# Power.net
KiCad netlist of a schematic drawn in Altium Designer
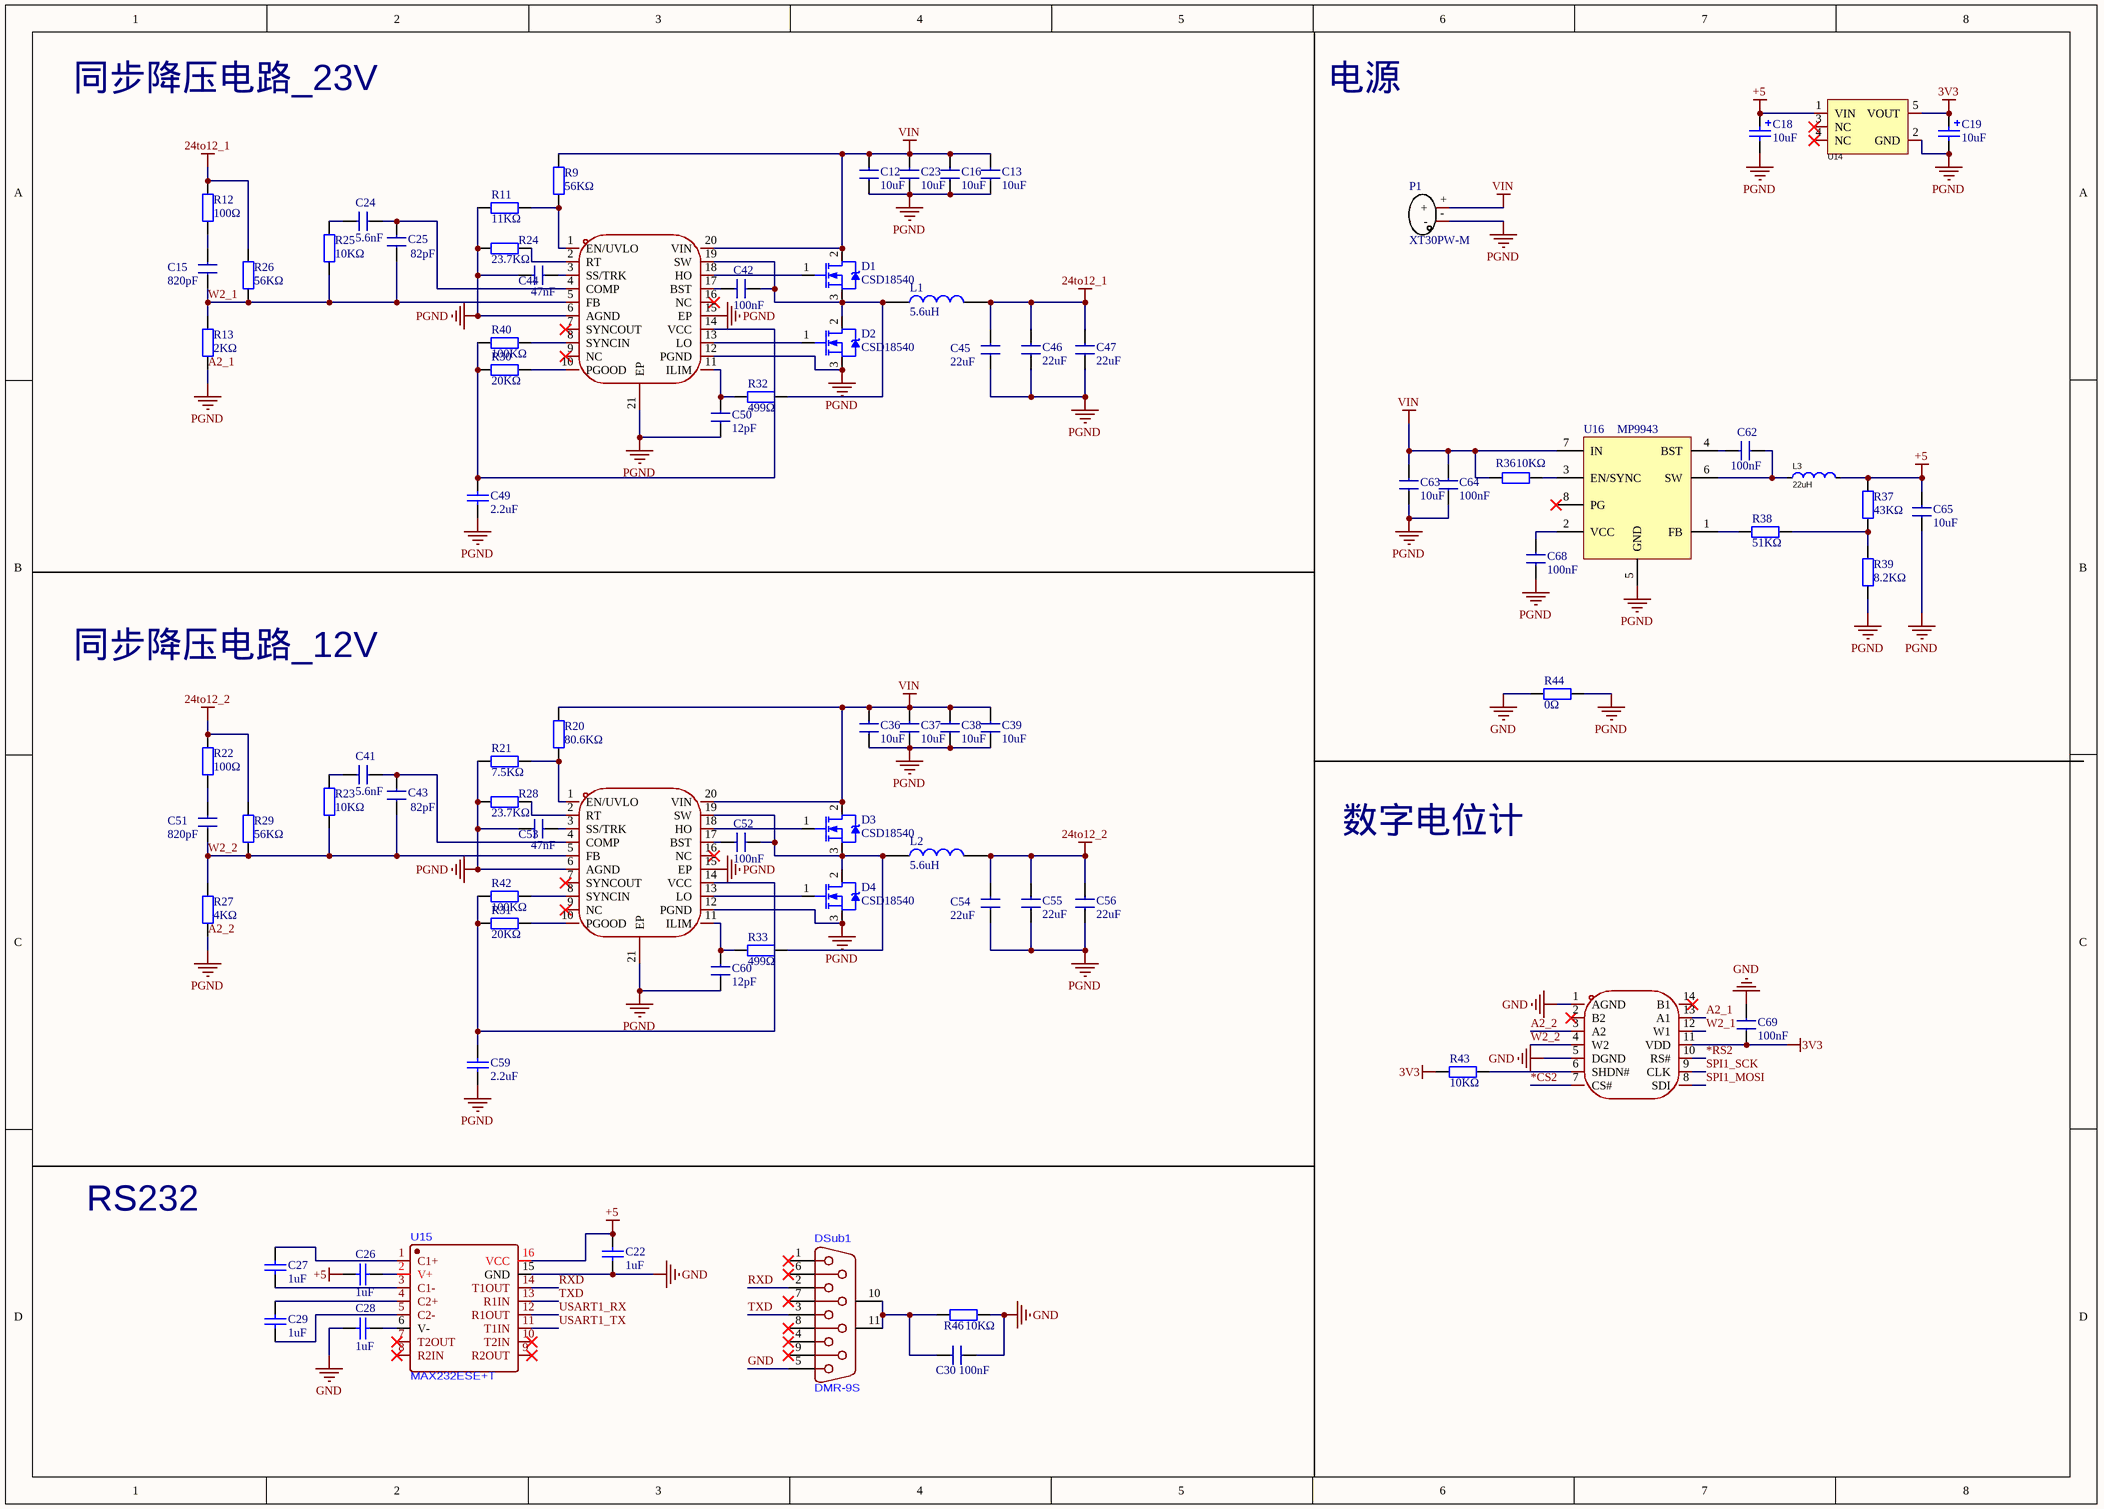
[diagram p0: Power.SchDoc]

(export (version "E")
  (design (tool "Eeschema 10.0.6"))
  (components
    (comp (ref "C12")
      (value "10uF")
      (footprint "1210")
      (description "1210贴片电容")
      (libsource (lib "Integrated_Library1") (part "1210贴片电容"))
    )
    (comp (ref "C13")
      (value "10uF")
      (footprint "1210")
      (description "1210贴片电容")
      (libsource (lib "En") (part "1210贴片电容"))
    )
    (comp (ref "C15")
      (value "820pF")
      (footprint "c0402")
      (description "贴片电容0402")
      (libsource (lib "Integrated_Library1") (part "0402贴片电容"))
    )
    (comp (ref "C16")
      (value "10uF")
      (footprint "1210")
      (description "1210贴片电容")
      (libsource (lib "En") (part "1210贴片电容"))
    )
    (comp (ref "C18")
      (value "10uF")
      (footprint "3216")
      (description "3216钽电容")
      (libsource (lib "Integrated_Library1") (part "3216钽电容"))
    )
    (comp (ref "C19")
      (value "10uF")
      (footprint "3216")
      (description "3216钽电容")
      (libsource (lib "Integrated_Library1") (part "3216钽电容"))
    )
    (comp (ref "C22")
      (value "1uF")
      (footprint "C 0603_M")
      (description "0603贴片电容")
      (libsource (lib "En") (part "0603贴片电容"))
    )
    (comp (ref "C23")
      (value "10uF")
      (footprint "1210")
      (description "1210贴片电容")
      (libsource (lib "En") (part "1210贴片电容"))
    )
    (comp (ref "C24")
      (value "5.6nF")
      (footprint "c0402")
      (description "贴片电容0402")
      (libsource (lib "Integrated_Library1") (part "0402贴片电容"))
    )
    (comp (ref "C25")
      (value "82pF")
      (footprint "c0402")
      (description "贴片电容0402")
      (libsource (lib "Integrated_Library1") (part "0402贴片电容"))
    )
    (comp (ref "C26")
      (value "1uF")
      (footprint "C 0603_M")
      (description "0603贴片电容")
      (libsource (lib "En") (part "0603贴片电容"))
    )
    (comp (ref "C27")
      (value "1uF")
      (footprint "C 0603_M")
      (description "0603贴片电容")
      (libsource (lib "En") (part "0603贴片电容"))
    )
    (comp (ref "C28")
      (value "1uF")
      (footprint "C 0603_M")
      (description "0603贴片电容")
      (libsource (lib "En") (part "0603贴片电容"))
    )
    (comp (ref "C29")
      (value "1uF")
      (footprint "C 0603_M")
      (description "0603贴片电容")
      (libsource (lib "En") (part "0603贴片电容"))
    )
    (comp (ref "C30")
      (value "100nF")
      (footprint "c0402")
      (description "贴片电容0402")
      (libsource (lib "Integrated_Library1") (part "0402贴片电容"))
    )
    (comp (ref "C36")
      (value "10uF")
      (footprint "1210")
      (description "1210贴片电容")
      (libsource (lib "Integrated_Library1") (part "1210贴片电容"))
    )
    (comp (ref "C37")
      (value "10uF")
      (footprint "1210")
      (description "1210贴片电容")
      (libsource (lib "En") (part "1210贴片电容"))
    )
    (comp (ref "C38")
      (value "10uF")
      (footprint "1210")
      (description "1210贴片电容")
      (libsource (lib "En") (part "1210贴片电容"))
    )
    (comp (ref "C39")
      (value "10uF")
      (footprint "1210")
      (description "1210贴片电容")
      (libsource (lib "En") (part "1210贴片电容"))
    )
    (comp (ref "C41")
      (value "5.6nF")
      (footprint "c0402")
      (description "贴片电容0402")
      (libsource (lib "Integrated_Library1") (part "0402贴片电容"))
    )
    (comp (ref "C42")
      (value "100nF")
      (footprint "C 0603_M")
      (description "贴片电容0402")
      (libsource (lib "Integrated_Library1") (part "0402贴片电容"))
    )
    (comp (ref "C43")
      (value "82pF")
      (footprint "c0402")
      (description "贴片电容0402")
      (libsource (lib "Integrated_Library1") (part "0402贴片电容"))
    )
    (comp (ref "C44")
      (value "47nF")
      (footprint "c0402")
      (description "贴片电容0402")
      (libsource (lib "Integrated_Library1") (part "0402贴片电容"))
    )
    (comp (ref "C45")
      (value "22uF")
      (footprint "1210")
      (description "1210贴片电容")
      (libsource (lib "En") (part "1210贴片电容"))
    )
    (comp (ref "C46")
      (value "22uF")
      (footprint "1210")
      (description "1210贴片电容")
      (libsource (lib "En") (part "1210贴片电容"))
    )
    (comp (ref "C47")
      (value "22uF")
      (footprint "1210")
      (description "1210贴片电容")
      (libsource (lib "En") (part "1210贴片电容"))
    )
    (comp (ref "C49")
      (value "2.2uF")
      (footprint "C 0603_M")
      (description "0603贴片电容")
      (libsource (lib "En") (part "0603贴片电容"))
    )
    (comp (ref "C50")
      (value "12pF")
      (footprint "c0402")
      (description "贴片电容0402")
      (libsource (lib "Integrated_Library1") (part "0402贴片电容"))
    )
    (comp (ref "C51")
      (value "820pF")
      (footprint "c0402")
      (description "贴片电容0402")
      (libsource (lib "Integrated_Library1") (part "0402贴片电容"))
    )
    (comp (ref "C52")
      (value "100nF")
      (footprint "C 0603_M")
      (description "贴片电容0402")
      (libsource (lib "Integrated_Library1") (part "0402贴片电容"))
    )
    (comp (ref "C53")
      (value "47nF")
      (footprint "c0402")
      (description "贴片电容0402")
      (libsource (lib "Integrated_Library1") (part "0402贴片电容"))
    )
    (comp (ref "C54")
      (value "22uF")
      (footprint "1210")
      (description "1210贴片电容")
      (libsource (lib "En") (part "1210贴片电容"))
    )
    (comp (ref "C55")
      (value "22uF")
      (footprint "1210")
      (description "1210贴片电容")
      (libsource (lib "En") (part "1210贴片电容"))
    )
    (comp (ref "C56")
      (value "22uF")
      (footprint "1210")
      (description "1210贴片电容")
      (libsource (lib "En") (part "1210贴片电容"))
    )
    (comp (ref "C59")
      (value "2.2uF")
      (footprint "C 0603_M")
      (description "0603贴片电容")
      (libsource (lib "En") (part "0603贴片电容"))
    )
    (comp (ref "C60")
      (value "12pF")
      (footprint "c0402")
      (description "贴片电容0402")
      (libsource (lib "Integrated_Library1") (part "0402贴片电容"))
    )
    (comp (ref "C62")
      (value "100nF")
      (footprint "c0402")
      (description "贴片电容0402")
      (libsource (lib "Integrated_Library1") (part "0402贴片电容"))
    )
    (comp (ref "C63")
      (value "10uF")
      (footprint "1210")
      (description "1210贴片电容")
      (libsource (lib "Integrated_Library1") (part "1210贴片电容"))
    )
    (comp (ref "C64")
      (value "100nF")
      (footprint "c0402")
      (description "贴片电容0402")
      (libsource (lib "Integrated_Library1") (part "0402贴片电容"))
    )
    (comp (ref "C65")
      (value "10uF")
      (footprint "1210")
      (description "1210贴片电容")
      (libsource (lib "Integrated_Library1") (part "1210贴片电容"))
    )
    (comp (ref "C68")
      (value "100nF")
      (footprint "c0402")
      (description "贴片电容0402")
      (libsource (lib "Integrated_Library1") (part "0402贴片电容"))
    )
    (comp (ref "C69")
      (value "100nF")
      (footprint "c0402")
      (description "贴片电容0402")
      (libsource (lib "Integrated_Library1") (part "0402贴片电容"))
    )
    (comp (ref "D1")
      (value "CSD18540")
      (footprint "pg-tdson-8")
      (description "N沟道MOS管")
      (fields (field (name "PUBLISHER") "Altium Limited"))
      (libsource (lib "En") (part "CSD18540"))
    )
    (comp (ref "D2")
      (value "CSD18540")
      (footprint "pg-tdson-8")
      (description "N沟道MOS管")
      (fields (field (name "PUBLISHER") "Altium Limited"))
      (libsource (lib "En") (part "CSD18540"))
    )
    (comp (ref "D3")
      (value "CSD18540")
      (footprint "pg-tdson-8")
      (description "N沟道MOS管")
      (fields (field (name "PUBLISHER") "Altium Limited"))
      (libsource (lib "En") (part "CSD18540"))
    )
    (comp (ref "D4")
      (value "CSD18540")
      (footprint "pg-tdson-8")
      (description "N沟道MOS管")
      (fields (field (name "PUBLISHER") "Altium Limited"))
      (libsource (lib "En") (part "CSD18540"))
    )
    (comp (ref "DSub1")
      (value "DMR-9S")
      (footprint "DSUB-TH_DMR-9S")
      (libsource (lib "Schlib1") (part "DMR-9S"))
    )
    (comp (ref "L1")
      (value "5.6uH")
      (footprint "L-SMD-0630")
      (description "一体成型屏蔽电感")
      (libsource (lib "En") (part "0630功率电感"))
    )
    (comp (ref "L2")
      (value "5.6uH")
      (footprint "L-SMD-0630")
      (description "一体成型屏蔽电感")
      (libsource (lib "En") (part "0630功率电感"))
    )
    (comp (ref "L3")
      (value "22uH")
      (footprint "IND-SMD_L5.4-W5.2")
      (description "一体成型屏蔽电感，0530封装，额定电流3A")
      (fields (field (name "MANUFACTURER") "XR(祥如)") (field (name "MANUFACTURER PART") "XR0530-100M"))
      (libsource (lib "En") (part "0530屏蔽电感"))
    )
    (comp (ref "P1")
      (value "XT30PW-M")
      (footprint "XT30PW-M")
      (description "卧式XT30母头")
      (fields (field (name "PUBLISHER") "Altium Limited"))
      (libsource (lib "Integrated_Library1") (part "卧式XT30母头"))
    )
    (comp (ref "R9")
      (value "56KΩ")
      (footprint "R0402")
      (description "0402贴片电阻")
      (libsource (lib "Integrated_Library1") (part "0402贴片电阻"))
    )
    (comp (ref "R11")
      (value "11KΩ")
      (footprint "R0402")
      (description "0402贴片电阻")
      (libsource (lib "") (part "0402贴片电阻_3"))
    )
    (comp (ref "R12")
      (value "100Ω")
      (footprint "R0402")
      (description "0402贴片电阻")
      (libsource (lib "") (part "0402贴片电阻_2"))
    )
    (comp (ref "R13")
      (value "2KΩ")
      (footprint "R0402")
      (description "0402贴片电阻")
      (libsource (lib "Integrated_Library1") (part "0402贴片电阻"))
    )
    (comp (ref "R20")
      (value "80.6KΩ")
      (footprint "R0402")
      (description "0402贴片电阻")
      (libsource (lib "Integrated_Library1") (part "0402贴片电阻"))
    )
    (comp (ref "R21")
      (value "7.5KΩ")
      (footprint "R0402")
      (description "0402贴片电阻")
      (libsource (lib "") (part "0402贴片电阻_3"))
    )
    (comp (ref "R22")
      (value "100Ω")
      (footprint "R0402")
      (description "0402贴片电阻")
      (libsource (lib "") (part "0402贴片电阻_2"))
    )
    (comp (ref "R23")
      (value "10KΩ")
      (footprint "R0402")
      (description "0402贴片电阻")
      (libsource (lib "") (part "0402贴片电阻_2"))
    )
    (comp (ref "R24")
      (value "23.7KΩ")
      (footprint "R0402")
      (description "0402贴片电阻")
      (libsource (lib "") (part "0402贴片电阻_1"))
    )
    (comp (ref "R25")
      (value "10KΩ")
      (footprint "R0402")
      (description "0402贴片电阻")
      (libsource (lib "") (part "0402贴片电阻_2"))
    )
    (comp (ref "R26")
      (value "56KΩ")
      (footprint "R0402")
      (description "0402贴片电阻")
      (libsource (lib "") (part "0402贴片电阻_2"))
    )
    (comp (ref "R27")
      (value "4KΩ")
      (footprint "R0402")
      (description "0402贴片电阻")
      (libsource (lib "Integrated_Library1") (part "0402贴片电阻"))
    )
    (comp (ref "R28")
      (value "23.7KΩ")
      (footprint "R0402")
      (description "0402贴片电阻")
      (libsource (lib "") (part "0402贴片电阻_1"))
    )
    (comp (ref "R29")
      (value "56KΩ")
      (footprint "R0402")
      (description "0402贴片电阻")
      (libsource (lib "") (part "0402贴片电阻_2"))
    )
    (comp (ref "R30")
      (value "20KΩ")
      (footprint "R0402")
      (description "0402贴片电阻")
      (libsource (lib "") (part "0402贴片电阻_1"))
    )
    (comp (ref "R31")
      (value "20KΩ")
      (footprint "R0402")
      (description "0402贴片电阻")
      (libsource (lib "") (part "0402贴片电阻_1"))
    )
    (comp (ref "R32")
      (value "499Ω")
      (footprint "R0402")
      (description "0402贴片电阻")
      (libsource (lib "") (part "0402贴片电阻_1"))
    )
    (comp (ref "R33")
      (value "499Ω")
      (footprint "R0402")
      (description "0402贴片电阻")
      (libsource (lib "") (part "0402贴片电阻_1"))
    )
    (comp (ref "R36")
      (value "10KΩ")
      (footprint "R0402")
      (description "0402贴片电阻")
      (libsource (lib "") (part "0402贴片电阻_3"))
    )
    (comp (ref "R37")
      (value "43KΩ")
      (footprint "R0402")
      (description "0402贴片电阻")
      (libsource (lib "") (part "0402贴片电阻_2"))
    )
    (comp (ref "R38")
      (value "51KΩ")
      (footprint "R0402")
      (description "0402贴片电阻")
      (libsource (lib "") (part "0402贴片电阻_3"))
    )
    (comp (ref "R39")
      (value "8.2KΩ")
      (footprint "R0402")
      (description "0402贴片电阻")
      (libsource (lib "") (part "0402贴片电阻_2"))
    )
    (comp (ref "R40")
      (value "100KΩ")
      (footprint "R0402")
      (description "0402贴片电阻")
      (libsource (lib "") (part "0402贴片电阻_1"))
    )
    (comp (ref "R42")
      (value "100KΩ")
      (footprint "R0402")
      (description "0402贴片电阻")
      (libsource (lib "") (part "0402贴片电阻_1"))
    )
    (comp (ref "R43")
      (value "10KΩ")
      (footprint "R0402")
      (description "0402贴片电阻")
      (libsource (lib "") (part "0402贴片电阻_1"))
    )
    (comp (ref "R44")
      (value "0Ω")
      (footprint "R0402")
      (description "0402贴片电阻")
      (libsource (lib "") (part "0402贴片电阻_3"))
    )
    (comp (ref "R46")
      (value "10KΩ")
      (footprint "R0402")
      (description "0402贴片电阻")
      (libsource (lib "") (part "0402贴片电阻_4"))
    )
    (comp (ref "U7")
      (value "LM25145RGYR")
      (footprint "VQFN-20_L4.5-W3.5-P0.50-BL-EP")
      (fields (field (name "MANUFACTURER") "TI(德州仪器)"))
      (libsource (lib "Schlib1") (part "LM25145RGYR"))
    )
    (comp (ref "U13")
      (value "LM25145RGYR")
      (footprint "VQFN-20_L4.5-W3.5-P0.50-BL-EP")
      (fields (field (name "MANUFACTURER") "TI(德州仪器)"))
      (libsource (lib "Schlib1") (part "LM25145RGYR"))
    )
    (comp (ref "U14")
      (value "XC6201P332MR-HXY")
      (footprint "SOT-23-5_L3.0-W1.7-P0.95-LS2.8-BR")
      (description "3.3V LDO")
      (fields (field (name "MANUFACTURER") "HXY MOSFET(华轩阳电子)"))
      (libsource (lib "Integrated_Library1") (part "XC6201P332MR-HXY"))
    )
    (comp (ref "U15")
      (value "MAX232ESE+T")
      (footprint "SOIC-16_L9.9-W3.9-P1.27-LS6.0-BL")
      (libsource (lib "Schlib1") (part "MAX232ESE+T"))
    )
    (comp (ref "U16")
      (value "MP9943")
      (footprint "QFN-8 3x3")
      (libsource (lib "Integrated_Library1") (part "MP9943"))
    )
    (comp (ref "U17")
      (value "AD8402ARZ10-REEL")
      (footprint "SOIC-14_L8.7-W3.9-P1.27-LS6.0-BL")
      (fields (field (name "MANUFACTURER") "ADI(亚德诺)"))
      (libsource (lib "Schlib1") (part "AD8402ARZ10-REEL"))
    )
  )
  (nets
    (net (code "1") (name "+5") (class "Default")
      (node (ref "C18") (pin "1") (pinfunction "1_1") (pintype "passive"))
      (node (ref "C22") (pin "2") (pinfunction "2_2") (pintype "passive"))
      (node (ref "C26") (pin "2") (pinfunction "2_2") (pintype "passive"))
      (node (ref "C65") (pin "2") (pinfunction "2_2") (pintype "passive"))
      (node (ref "L3") (pin "2") (pinfunction "2_2") (pintype "passive"))
      (node (ref "R37") (pin "2") (pinfunction "2_2") (pintype "passive"))
      (node (ref "U14") (pin "1") (pinfunction "VIN_1") (pintype "passive"))
      (node (ref "U15") (pin "16") (pinfunction "VCC_16") (pintype "passive"))
    )
    (net (code "2") (name "/*CS2") (class "Default")
      (node (ref "U17") (pin "7") (pinfunction "CS#_7") (pintype "passive"))
    )
    (net (code "3") (name "/*RS2") (class "Default")
      (node (ref "U17") (pin "10") (pinfunction "RS#_10") (pintype "passive"))
    )
    (net (code "4") (name "/RXD") (class "Default")
      (node (ref "DSub1") (pin "2") (pinfunction "2_2") (pintype "passive"))
      (node (ref "U15") (pin "14") (pinfunction "T1OUT_14") (pintype "passive"))
    )
    (net (code "5") (name "/SPI1_MOSI") (class "Default")
      (node (ref "U17") (pin "8") (pinfunction "SDI_8") (pintype "passive"))
    )
    (net (code "6") (name "/SPI1_SCK") (class "Default")
      (node (ref "U17") (pin "9") (pinfunction "CLK_9") (pintype "passive"))
    )
    (net (code "7") (name "/TXD") (class "Default")
      (node (ref "DSub1") (pin "3") (pinfunction "3_3") (pintype "passive"))
      (node (ref "U15") (pin "13") (pinfunction "R1IN_13") (pintype "passive"))
    )
    (net (code "8") (name "/USART1_RX") (class "Default")
      (node (ref "U15") (pin "12") (pinfunction "R1OUT_12") (pintype "passive"))
    )
    (net (code "9") (name "/USART1_TX") (class "Default")
      (node (ref "U15") (pin "11") (pinfunction "T1IN_11") (pintype "passive"))
    )
    (net (code "10") (name "/W2_1") (class "Default")
      (node (ref "C15") (pin "2") (pinfunction "2_2") (pintype "passive"))
      (node (ref "C25") (pin "1") (pinfunction "1_1") (pintype "passive"))
      (node (ref "R13") (pin "1") (pinfunction "1_1") (pintype "passive"))
      (node (ref "R25") (pin "1") (pinfunction "1_1") (pintype "passive"))
      (node (ref "R26") (pin "1") (pinfunction "1_1") (pintype "passive"))
      (node (ref "U13") (pin "5") (pinfunction "FB_5") (pintype "passive"))
      (node (ref "U17") (pin "12") (pinfunction "W1_12") (pintype "passive"))
    )
    (net (code "11") (name "/W2_2") (class "Default")
      (node (ref "C43") (pin "1") (pinfunction "1_1") (pintype "passive"))
      (node (ref "C51") (pin "2") (pinfunction "2_2") (pintype "passive"))
      (node (ref "R23") (pin "1") (pinfunction "1_1") (pintype "passive"))
      (node (ref "R27") (pin "1") (pinfunction "1_1") (pintype "passive"))
      (node (ref "R29") (pin "1") (pinfunction "1_1") (pintype "passive"))
      (node (ref "U17") (pin "4") (pinfunction "W2_4") (pintype "passive"))
      (node (ref "U7") (pin "5") (pinfunction "FB_5") (pintype "passive"))
    )
    (net (code "12") (name "3V3") (class "Default")
      (node (ref "C19") (pin "1") (pinfunction "1_1") (pintype "passive"))
      (node (ref "C69") (pin "2") (pinfunction "2_2") (pintype "passive"))
      (node (ref "R43") (pin "2") (pinfunction "2_2") (pintype "passive"))
      (node (ref "U14") (pin "5") (pinfunction "VOUT_5") (pintype "passive"))
      (node (ref "U17") (pin "11") (pinfunction "VDD_11") (pintype "passive"))
    )
    (net (code "13") (name "24to12_1") (class "Default")
      (node (ref "C45") (pin "2") (pinfunction "2_2") (pintype "passive"))
      (node (ref "C46") (pin "2") (pinfunction "2_2") (pintype "passive"))
      (node (ref "C47") (pin "2") (pinfunction "2_2") (pintype "passive"))
      (node (ref "L1") (pin "2") (pinfunction "2_2") (pintype "passive"))
      (node (ref "R12") (pin "2") (pinfunction "2_2") (pintype "passive"))
      (node (ref "R26") (pin "2") (pinfunction "2_2") (pintype "passive"))
    )
    (net (code "14") (name "24to12_2") (class "Default")
      (node (ref "C54") (pin "2") (pinfunction "2_2") (pintype "passive"))
      (node (ref "C55") (pin "2") (pinfunction "2_2") (pintype "passive"))
      (node (ref "C56") (pin "2") (pinfunction "2_2") (pintype "passive"))
      (node (ref "L2") (pin "2") (pinfunction "2_2") (pintype "passive"))
      (node (ref "R22") (pin "2") (pinfunction "2_2") (pintype "passive"))
      (node (ref "R29") (pin "2") (pinfunction "2_2") (pintype "passive"))
    )
    (net (code "15") (name "GND") (class "Default")
      (node (ref "C22") (pin "1") (pinfunction "1_1") (pintype "passive"))
      (node (ref "C28") (pin "2") (pinfunction "2_2") (pintype "passive"))
      (node (ref "C30") (pin "2") (pinfunction "2_2") (pintype "passive"))
      (node (ref "C69") (pin "1") (pinfunction "1_1") (pintype "passive"))
      (node (ref "DSub1") (pin "5") (pinfunction "5_5") (pintype "passive"))
      (node (ref "R44") (pin "1") (pinfunction "1_1") (pintype "passive"))
      (node (ref "R46") (pin "2") (pinfunction "2_2") (pintype "passive"))
      (node (ref "U15") (pin "15") (pinfunction "GND_15") (pintype "passive"))
      (node (ref "U17") (pin "1") (pinfunction "AGND_1") (pintype "passive"))
      (node (ref "U17") (pin "5") (pinfunction "DGND_5") (pintype "passive"))
    )
    (net (code "16") (name "Net-(C15-Pad1)") (class "Default")
      (node (ref "C15") (pin "1") (pinfunction "1_1") (pintype "passive"))
      (node (ref "R12") (pin "1") (pinfunction "1_1") (pintype "passive"))
    )
    (net (code "17") (name "Net-(C24-Pad2)") (class "Default")
      (node (ref "C24") (pin "2") (pinfunction "2_2") (pintype "passive"))
      (node (ref "R25") (pin "2") (pinfunction "2_2") (pintype "passive"))
    )
    (net (code "18") (name "Net-(C41-Pad2)") (class "Default")
      (node (ref "C41") (pin "2") (pinfunction "2_2") (pintype "passive"))
      (node (ref "R23") (pin "2") (pinfunction "2_2") (pintype "passive"))
    )
    (net (code "19") (name "Net-(C51-Pad1)") (class "Default")
      (node (ref "C51") (pin "1") (pinfunction "1_1") (pintype "passive"))
      (node (ref "R22") (pin "1") (pinfunction "1_1") (pintype "passive"))
    )
    (net (code "20") (name "Net-(D1-G)") (class "Default")
      (node (ref "D1") (pin "1") (pinfunction "G_1") (pintype "passive"))
      (node (ref "U13") (pin "18") (pinfunction "HO_18") (pintype "passive"))
    )
    (net (code "21") (name "Net-(D1-S)") (class "Default")
      (node (ref "C42") (pin "1") (pinfunction "1_1") (pintype "passive"))
      (node (ref "D1") (pin "3") (pinfunction "S_3") (pintype "passive"))
      (node (ref "D2") (pin "2") (pinfunction "D_2") (pintype "passive"))
      (node (ref "L1") (pin "1") (pinfunction "1_1") (pintype "passive"))
      (node (ref "R32") (pin "1") (pinfunction "1_1") (pintype "passive"))
      (node (ref "U13") (pin "19") (pinfunction "SW_19") (pintype "passive"))
    )
    (net (code "22") (name "Net-(D2-G)") (class "Default")
      (node (ref "D2") (pin "1") (pinfunction "G_1") (pintype "passive"))
      (node (ref "U13") (pin "13") (pinfunction "LO_13") (pintype "passive"))
    )
    (net (code "23") (name "Net-(D3-G)") (class "Default")
      (node (ref "D3") (pin "1") (pinfunction "G_1") (pintype "passive"))
      (node (ref "U7") (pin "18") (pinfunction "HO_18") (pintype "passive"))
    )
    (net (code "24") (name "Net-(D3-S)") (class "Default")
      (node (ref "C52") (pin "1") (pinfunction "1_1") (pintype "passive"))
      (node (ref "D3") (pin "3") (pinfunction "S_3") (pintype "passive"))
      (node (ref "D4") (pin "2") (pinfunction "D_2") (pintype "passive"))
      (node (ref "L2") (pin "1") (pinfunction "1_1") (pintype "passive"))
      (node (ref "R33") (pin "1") (pinfunction "1_1") (pintype "passive"))
      (node (ref "U7") (pin "19") (pinfunction "SW_19") (pintype "passive"))
    )
    (net (code "25") (name "Net-(D4-G)") (class "Default")
      (node (ref "D4") (pin "1") (pinfunction "G_1") (pintype "passive"))
      (node (ref "U7") (pin "13") (pinfunction "LO_13") (pintype "passive"))
    )
    (net (code "26") (name "Net-(DSub1-MH1)") (class "Default")
      (node (ref "C30") (pin "1") (pinfunction "1_1") (pintype "passive"))
      (node (ref "DSub1") (pin "10") (pinfunction "MH1_10") (pintype "passive"))
      (node (ref "DSub1") (pin "11") (pinfunction "MH2_11") (pintype "passive"))
      (node (ref "R46") (pin "1") (pinfunction "1_1") (pintype "passive"))
    )
    (net (code "27") (name "Net-(R37-Pad1)") (class "Default")
      (node (ref "R37") (pin "1") (pinfunction "1_1") (pintype "passive"))
      (node (ref "R38") (pin "2") (pinfunction "2_2") (pintype "passive"))
      (node (ref "R39") (pin "2") (pinfunction "2_2") (pintype "passive"))
    )
    (net (code "28") (name "Net-(U7-BST)") (class "Default")
      (node (ref "C52") (pin "2") (pinfunction "2_2") (pintype "passive"))
      (node (ref "U7") (pin "17") (pinfunction "BST_17") (pintype "passive"))
    )
    (net (code "29") (name "Net-(U7-COMP)") (class "Default")
      (node (ref "C41") (pin "1") (pinfunction "1_1") (pintype "passive"))
      (node (ref "C43") (pin "2") (pinfunction "2_2") (pintype "passive"))
      (node (ref "U7") (pin "4") (pinfunction "COMP_4") (pintype "passive"))
    )
    (net (code "30") (name "Net-(U7-EN{slash}UVLO)") (class "Default")
      (node (ref "R20") (pin "2") (pinfunction "2_2") (pintype "passive"))
      (node (ref "R21") (pin "2") (pinfunction "2_2") (pintype "passive"))
      (node (ref "U7") (pin "1") (pinfunction "EN/UVLO_1") (pintype "passive"))
    )
    (net (code "31") (name "Net-(U7-ILIM)") (class "Default")
      (node (ref "C60") (pin "2") (pinfunction "2_2") (pintype "passive"))
      (node (ref "R33") (pin "2") (pinfunction "2_2") (pintype "passive"))
      (node (ref "U7") (pin "11") (pinfunction "ILIM_11") (pintype "passive"))
    )
    (net (code "32") (name "Net-(U7-PGOOD)") (class "Default")
      (node (ref "R31") (pin "1") (pinfunction "1_1") (pintype "passive"))
      (node (ref "U7") (pin "10") (pinfunction "PGOOD_10") (pintype "passive"))
    )
    (net (code "33") (name "Net-(U7-RT)") (class "Default")
      (node (ref "R28") (pin "1") (pinfunction "1_1") (pintype "passive"))
      (node (ref "U7") (pin "2") (pinfunction "RT_2") (pintype "passive"))
    )
    (net (code "34") (name "Net-(U7-SS{slash}TRK)") (class "Default")
      (node (ref "C53") (pin "1") (pinfunction "1_1") (pintype "passive"))
      (node (ref "U7") (pin "3") (pinfunction "SS/TRK_3") (pintype "passive"))
    )
    (net (code "35") (name "Net-(U7-SYNCIN)") (class "Default")
      (node (ref "R42") (pin "1") (pinfunction "1_1") (pintype "passive"))
      (node (ref "U7") (pin "8") (pinfunction "SYNCIN_8") (pintype "passive"))
    )
    (net (code "36") (name "Net-(U7-VCC)") (class "Default")
      (node (ref "C59") (pin "2") (pinfunction "2_2") (pintype "passive"))
      (node (ref "R31") (pin "2") (pinfunction "2_2") (pintype "passive"))
      (node (ref "R42") (pin "2") (pinfunction "2_2") (pintype "passive"))
      (node (ref "U7") (pin "14") (pinfunction "VCC_14") (pintype "passive"))
    )
    (net (code "37") (name "Net-(U13-BST)") (class "Default")
      (node (ref "C42") (pin "2") (pinfunction "2_2") (pintype "passive"))
      (node (ref "U13") (pin "17") (pinfunction "BST_17") (pintype "passive"))
    )
    (net (code "38") (name "Net-(U13-COMP)") (class "Default")
      (node (ref "C24") (pin "1") (pinfunction "1_1") (pintype "passive"))
      (node (ref "C25") (pin "2") (pinfunction "2_2") (pintype "passive"))
      (node (ref "U13") (pin "4") (pinfunction "COMP_4") (pintype "passive"))
    )
    (net (code "39") (name "Net-(U13-EN{slash}UVLO)") (class "Default")
      (node (ref "R11") (pin "2") (pinfunction "2_2") (pintype "passive"))
      (node (ref "R9") (pin "2") (pinfunction "2_2") (pintype "passive"))
      (node (ref "U13") (pin "1") (pinfunction "EN/UVLO_1") (pintype "passive"))
    )
    (net (code "40") (name "Net-(U13-ILIM)") (class "Default")
      (node (ref "C50") (pin "2") (pinfunction "2_2") (pintype "passive"))
      (node (ref "R32") (pin "2") (pinfunction "2_2") (pintype "passive"))
      (node (ref "U13") (pin "11") (pinfunction "ILIM_11") (pintype "passive"))
    )
    (net (code "41") (name "Net-(U13-PGOOD)") (class "Default")
      (node (ref "R30") (pin "1") (pinfunction "1_1") (pintype "passive"))
      (node (ref "U13") (pin "10") (pinfunction "PGOOD_10") (pintype "passive"))
    )
    (net (code "42") (name "Net-(U13-RT)") (class "Default")
      (node (ref "R24") (pin "1") (pinfunction "1_1") (pintype "passive"))
      (node (ref "U13") (pin "2") (pinfunction "RT_2") (pintype "passive"))
    )
    (net (code "43") (name "Net-(U13-SS{slash}TRK)") (class "Default")
      (node (ref "C44") (pin "1") (pinfunction "1_1") (pintype "passive"))
      (node (ref "U13") (pin "3") (pinfunction "SS/TRK_3") (pintype "passive"))
    )
    (net (code "44") (name "Net-(U13-SYNCIN)") (class "Default")
      (node (ref "R40") (pin "1") (pinfunction "1_1") (pintype "passive"))
      (node (ref "U13") (pin "8") (pinfunction "SYNCIN_8") (pintype "passive"))
    )
    (net (code "45") (name "Net-(U13-VCC)") (class "Default")
      (node (ref "C49") (pin "2") (pinfunction "2_2") (pintype "passive"))
      (node (ref "R30") (pin "2") (pinfunction "2_2") (pintype "passive"))
      (node (ref "R40") (pin "2") (pinfunction "2_2") (pintype "passive"))
      (node (ref "U13") (pin "14") (pinfunction "VCC_14") (pintype "passive"))
    )
    (net (code "46") (name "Net-(U15-C1+)") (class "Default")
      (node (ref "C27") (pin "1") (pinfunction "1_1") (pintype "passive"))
      (node (ref "U15") (pin "1") (pinfunction "C1+_1") (pintype "passive"))
    )
    (net (code "47") (name "Net-(U15-C1-)") (class "Default")
      (node (ref "C27") (pin "2") (pinfunction "2_2") (pintype "passive"))
      (node (ref "U15") (pin "3") (pinfunction "C1-_3") (pintype "passive"))
    )
    (net (code "48") (name "Net-(U15-C2+)") (class "Default")
      (node (ref "C29") (pin "1") (pinfunction "1_1") (pintype "passive"))
      (node (ref "U15") (pin "4") (pinfunction "C2+_4") (pintype "passive"))
    )
    (net (code "49") (name "Net-(U15-C2-)") (class "Default")
      (node (ref "C29") (pin "2") (pinfunction "2_2") (pintype "passive"))
      (node (ref "U15") (pin "5") (pinfunction "C2-_5") (pintype "passive"))
    )
    (net (code "50") (name "Net-(U15-V+)") (class "Default")
      (node (ref "C26") (pin "1") (pinfunction "1_1") (pintype "passive"))
      (node (ref "U15") (pin "2") (pinfunction "V+_2") (pintype "passive"))
    )
    (net (code "51") (name "Net-(U15-V-)") (class "Default")
      (node (ref "C28") (pin "1") (pinfunction "1_1") (pintype "passive"))
      (node (ref "U15") (pin "6") (pinfunction "V-_6") (pintype "passive"))
    )
    (net (code "52") (name "Net-(U16-BST)") (class "Default")
      (node (ref "C62") (pin "1") (pinfunction "1_1") (pintype "passive"))
      (node (ref "U16") (pin "4") (pinfunction "BST_4") (pintype "passive"))
    )
    (net (code "53") (name "Net-(U16-EN{slash}SYNC)") (class "Default")
      (node (ref "R36") (pin "2") (pinfunction "2_2") (pintype "passive"))
      (node (ref "U16") (pin "3") (pinfunction "EN/SYNC_3") (pintype "passive"))
    )
    (net (code "54") (name "Net-(U16-FB)") (class "Default")
      (node (ref "R38") (pin "1") (pinfunction "1_1") (pintype "passive"))
      (node (ref "U16") (pin "1") (pinfunction "FB_1") (pintype "passive"))
    )
    (net (code "55") (name "Net-(U16-SW)") (class "Default")
      (node (ref "C62") (pin "2") (pinfunction "2_2") (pintype "passive"))
      (node (ref "L3") (pin "1") (pinfunction "1_1") (pintype "passive"))
      (node (ref "U16") (pin "6") (pinfunction "SW_6") (pintype "passive"))
    )
    (net (code "56") (name "Net-(U16-VCC)") (class "Default")
      (node (ref "C68") (pin "2") (pinfunction "2_2") (pintype "passive"))
      (node (ref "U16") (pin "2") (pinfunction "VCC_2") (pintype "passive"))
    )
    (net (code "57") (name "Net-(U17-SHDN#)") (class "Default")
      (node (ref "R43") (pin "1") (pinfunction "1_1") (pintype "passive"))
      (node (ref "U17") (pin "6") (pinfunction "SHDN#_6") (pintype "passive"))
    )
    (net (code "58") (name "PGND") (class "Default")
      (node (ref "C12") (pin "1") (pinfunction "1_1") (pintype "passive"))
      (node (ref "C13") (pin "1") (pinfunction "1_1") (pintype "passive"))
      (node (ref "C16") (pin "1") (pinfunction "1_1") (pintype "passive"))
      (node (ref "C18") (pin "2") (pinfunction "2_2") (pintype "passive"))
      (node (ref "C19") (pin "2") (pinfunction "2_2") (pintype "passive"))
      (node (ref "C23") (pin "1") (pinfunction "1_1") (pintype "passive"))
      (node (ref "C36") (pin "1") (pinfunction "1_1") (pintype "passive"))
      (node (ref "C37") (pin "1") (pinfunction "1_1") (pintype "passive"))
      (node (ref "C38") (pin "1") (pinfunction "1_1") (pintype "passive"))
      (node (ref "C39") (pin "1") (pinfunction "1_1") (pintype "passive"))
      (node (ref "C44") (pin "2") (pinfunction "2_2") (pintype "passive"))
      (node (ref "C45") (pin "1") (pinfunction "1_1") (pintype "passive"))
      (node (ref "C46") (pin "1") (pinfunction "1_1") (pintype "passive"))
      (node (ref "C47") (pin "1") (pinfunction "1_1") (pintype "passive"))
      (node (ref "C49") (pin "1") (pinfunction "1_1") (pintype "passive"))
      (node (ref "C50") (pin "1") (pinfunction "1_1") (pintype "passive"))
      (node (ref "C53") (pin "2") (pinfunction "2_2") (pintype "passive"))
      (node (ref "C54") (pin "1") (pinfunction "1_1") (pintype "passive"))
      (node (ref "C55") (pin "1") (pinfunction "1_1") (pintype "passive"))
      (node (ref "C56") (pin "1") (pinfunction "1_1") (pintype "passive"))
      (node (ref "C59") (pin "1") (pinfunction "1_1") (pintype "passive"))
      (node (ref "C60") (pin "1") (pinfunction "1_1") (pintype "passive"))
      (node (ref "C63") (pin "1") (pinfunction "1_1") (pintype "passive"))
      (node (ref "C64") (pin "1") (pinfunction "1_1") (pintype "passive"))
      (node (ref "C65") (pin "1") (pinfunction "1_1") (pintype "passive"))
      (node (ref "C68") (pin "1") (pinfunction "1_1") (pintype "passive"))
      (node (ref "D2") (pin "3") (pinfunction "S_3") (pintype "passive"))
      (node (ref "D4") (pin "3") (pinfunction "S_3") (pintype "passive"))
      (node (ref "P1") (pin "-") (pinfunction "-_-") (pintype "passive"))
      (node (ref "R11") (pin "1") (pinfunction "1_1") (pintype "passive"))
      (node (ref "R13") (pin "2") (pinfunction "2_2") (pintype "passive"))
      (node (ref "R21") (pin "1") (pinfunction "1_1") (pintype "passive"))
      (node (ref "R24") (pin "2") (pinfunction "2_2") (pintype "passive"))
      (node (ref "R27") (pin "2") (pinfunction "2_2") (pintype "passive"))
      (node (ref "R28") (pin "2") (pinfunction "2_2") (pintype "passive"))
      (node (ref "R39") (pin "1") (pinfunction "1_1") (pintype "passive"))
      (node (ref "R44") (pin "2") (pinfunction "2_2") (pintype "passive"))
      (node (ref "U13") (pin "12") (pinfunction "PGND_12") (pintype "passive"))
      (node (ref "U13") (pin "15") (pinfunction "EP_15") (pintype "passive"))
      (node (ref "U13") (pin "21") (pinfunction "EP_21") (pintype "passive"))
      (node (ref "U13") (pin "6") (pinfunction "AGND_6") (pintype "passive"))
      (node (ref "U14") (pin "2") (pinfunction "GND_2") (pintype "passive"))
      (node (ref "U16") (pin "5") (pinfunction "GND_5") (pintype "passive"))
      (node (ref "U17") (pin "13") (pinfunction "A1_13") (pintype "passive"))
      (node (ref "U17") (pin "3") (pinfunction "A2_3") (pintype "passive"))
      (node (ref "U7") (pin "12") (pinfunction "PGND_12") (pintype "passive"))
      (node (ref "U7") (pin "15") (pinfunction "EP_15") (pintype "passive"))
      (node (ref "U7") (pin "21") (pinfunction "EP_21") (pintype "passive"))
      (node (ref "U7") (pin "6") (pinfunction "AGND_6") (pintype "passive"))
    )
    (net (code "59") (name "VIN") (class "Default")
      (node (ref "C12") (pin "2") (pinfunction "2_2") (pintype "passive"))
      (node (ref "C13") (pin "2") (pinfunction "2_2") (pintype "passive"))
      (node (ref "C16") (pin "2") (pinfunction "2_2") (pintype "passive"))
      (node (ref "C23") (pin "2") (pinfunction "2_2") (pintype "passive"))
      (node (ref "C36") (pin "2") (pinfunction "2_2") (pintype "passive"))
      (node (ref "C37") (pin "2") (pinfunction "2_2") (pintype "passive"))
      (node (ref "C38") (pin "2") (pinfunction "2_2") (pintype "passive"))
      (node (ref "C39") (pin "2") (pinfunction "2_2") (pintype "passive"))
      (node (ref "C63") (pin "2") (pinfunction "2_2") (pintype "passive"))
      (node (ref "C64") (pin "2") (pinfunction "2_2") (pintype "passive"))
      (node (ref "D1") (pin "2") (pinfunction "D_2") (pintype "passive"))
      (node (ref "D3") (pin "2") (pinfunction "D_2") (pintype "passive"))
      (node (ref "P1") (pin "+") (pinfunction "+_+") (pintype "passive"))
      (node (ref "R20") (pin "1") (pinfunction "1_1") (pintype "passive"))
      (node (ref "R36") (pin "1") (pinfunction "1_1") (pintype "passive"))
      (node (ref "R9") (pin "1") (pinfunction "1_1") (pintype "passive"))
      (node (ref "U13") (pin "20") (pinfunction "VIN_20") (pintype "passive"))
      (node (ref "U16") (pin "7") (pinfunction "IN_7") (pintype "passive"))
      (node (ref "U7") (pin "20") (pinfunction "VIN_20") (pintype "passive"))
    )
    (net (code "60") (name "unconnected-(DSub1-Pad1)") (class "Default")
      (node (ref "DSub1") (pin "1") (pinfunction "1_1") (pintype "passive+no_connect"))
    )
    (net (code "61") (name "unconnected-(DSub1-Pad4)") (class "Default")
      (node (ref "DSub1") (pin "4") (pinfunction "4_4") (pintype "passive+no_connect"))
    )
    (net (code "62") (name "unconnected-(DSub1-Pad6)") (class "Default")
      (node (ref "DSub1") (pin "6") (pinfunction "6_6") (pintype "passive+no_connect"))
    )
    (net (code "63") (name "unconnected-(DSub1-Pad7)") (class "Default")
      (node (ref "DSub1") (pin "7") (pinfunction "7_7") (pintype "passive+no_connect"))
    )
    (net (code "64") (name "unconnected-(DSub1-Pad8)") (class "Default")
      (node (ref "DSub1") (pin "8") (pinfunction "8_8") (pintype "passive+no_connect"))
    )
    (net (code "65") (name "unconnected-(DSub1-Pad9)") (class "Default")
      (node (ref "DSub1") (pin "9") (pinfunction "9_9") (pintype "passive+no_connect"))
    )
    (net (code "66") (name "unconnected-(U7-NC-Pad9)") (class "Default")
      (node (ref "U7") (pin "9") (pinfunction "NC_9") (pintype "passive+no_connect"))
    )
    (net (code "67") (name "unconnected-(U7-NC-Pad16)") (class "Default")
      (node (ref "U7") (pin "16") (pinfunction "NC_16") (pintype "passive+no_connect"))
    )
    (net (code "68") (name "unconnected-(U7-SYNCOUT-Pad7)") (class "Default")
      (node (ref "U7") (pin "7") (pinfunction "SYNCOUT_7") (pintype "passive+no_connect"))
    )
    (net (code "69") (name "unconnected-(U13-NC-Pad9)") (class "Default")
      (node (ref "U13") (pin "9") (pinfunction "NC_9") (pintype "passive+no_connect"))
    )
    (net (code "70") (name "unconnected-(U13-NC-Pad16)") (class "Default")
      (node (ref "U13") (pin "16") (pinfunction "NC_16") (pintype "passive+no_connect"))
    )
    (net (code "71") (name "unconnected-(U13-SYNCOUT-Pad7)") (class "Default")
      (node (ref "U13") (pin "7") (pinfunction "SYNCOUT_7") (pintype "passive+no_connect"))
    )
    (net (code "72") (name "unconnected-(U14-NC-Pad3)") (class "Default")
      (node (ref "U14") (pin "3") (pinfunction "NC_3") (pintype "passive+no_connect"))
    )
    (net (code "73") (name "unconnected-(U14-NC-Pad4)") (class "Default")
      (node (ref "U14") (pin "4") (pinfunction "NC_4") (pintype "passive+no_connect"))
    )
    (net (code "74") (name "unconnected-(U15-R2IN-Pad8)") (class "Default")
      (node (ref "U15") (pin "8") (pinfunction "R2IN_8") (pintype "passive+no_connect"))
    )
    (net (code "75") (name "unconnected-(U15-R2OUT-Pad9)") (class "Default")
      (node (ref "U15") (pin "9") (pinfunction "R2OUT_9") (pintype "passive+no_connect"))
    )
    (net (code "76") (name "unconnected-(U15-T2IN-Pad10)") (class "Default")
      (node (ref "U15") (pin "10") (pinfunction "T2IN_10") (pintype "passive+no_connect"))
    )
    (net (code "77") (name "unconnected-(U15-T2OUT-Pad7)") (class "Default")
      (node (ref "U15") (pin "7") (pinfunction "T2OUT_7") (pintype "passive+no_connect"))
    )
    (net (code "78") (name "unconnected-(U16-PG-Pad8)") (class "Default")
      (node (ref "U16") (pin "8") (pinfunction "PG_8") (pintype "passive+no_connect"))
    )
    (net (code "79") (name "unconnected-(U17-B1-Pad14)") (class "Default")
      (node (ref "U17") (pin "14") (pinfunction "B1_14") (pintype "passive+no_connect"))
    )
    (net (code "80") (name "unconnected-(U17-B2-Pad2)") (class "Default")
      (node (ref "U17") (pin "2") (pinfunction "B2_2") (pintype "passive+no_connect"))
    )
  )
)
